# poti_encoder.net
KiCad netlist of a schematic drawn in EAGLE
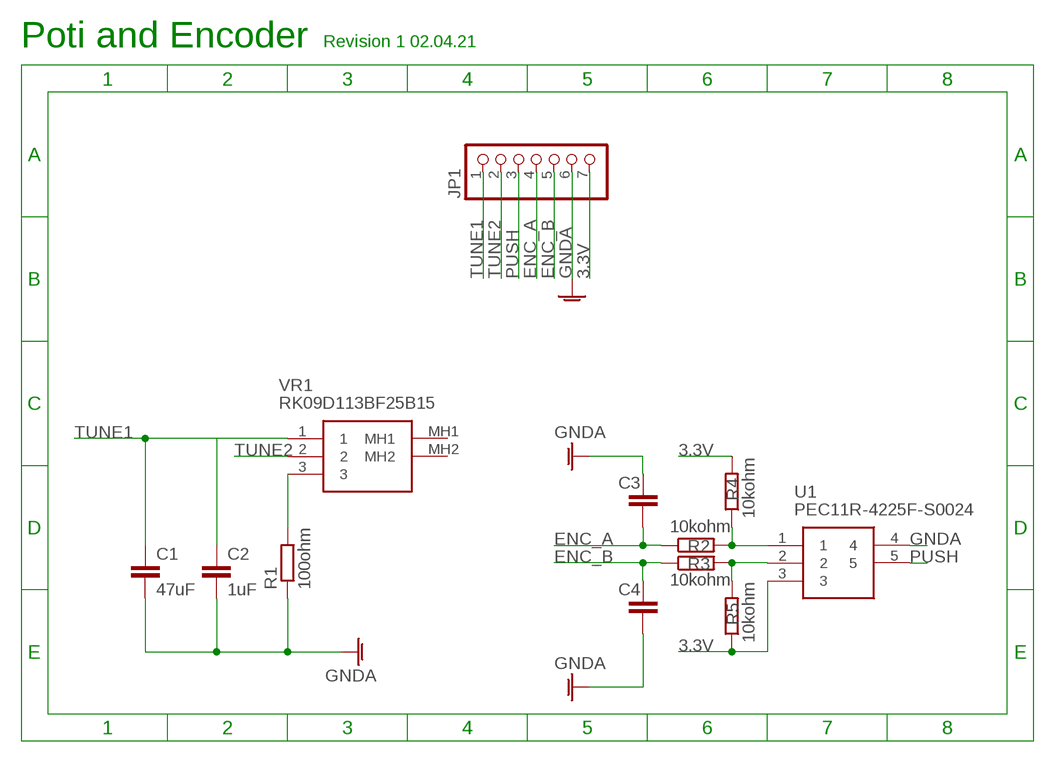
[diagram p0: schematic, sheet 1]

(export (version "E")
  (design (tool "Eeschema 10.0.6"))
  (components
    (comp (ref "C1")
      (value "47uF")
      (footprint "eagle-import:C1206")
      (libsource (lib "eagle-import") (part "C-EU_1206C1206"))
    )
    (comp (ref "C2")
      (value "1uF")
      (footprint "eagle-import:C0805")
      (libsource (lib "eagle-import") (part "C-EU_805C0805"))
    )
    (comp (ref "C3")
      (value "C-EU_805C0805")
      (footprint "eagle-import:C0805")
      (libsource (lib "eagle-import") (part "C-EU_805C0805"))
    )
    (comp (ref "C4")
      (value "C-EU_805C0805")
      (footprint "eagle-import:C0805")
      (libsource (lib "eagle-import") (part "C-EU_805C0805"))
    )
    (comp (ref "JP1")
      (value "PINHD-1X7")
      (footprint "eagle-import:1X07")
      (libsource (lib "eagle-import") (part "PINHD-1X7"))
    )
    (comp (ref "R1")
      (value "100ohm")
      (footprint "eagle-import:R0805")
      (libsource (lib "eagle-import") (part "R-EU_805R0805"))
    )
    (comp (ref "R2")
      (value "10kohm")
      (footprint "eagle-import:R0805")
      (libsource (lib "eagle-import") (part "R-EU_805R0805"))
    )
    (comp (ref "R3")
      (value "10kohm")
      (footprint "eagle-import:R0805")
      (libsource (lib "eagle-import") (part "R-EU_805R0805"))
    )
    (comp (ref "R4")
      (value "10kohm")
      (footprint "eagle-import:R0805")
      (libsource (lib "eagle-import") (part "R-EU_805R0805"))
    )
    (comp (ref "R5")
      (value "10kohm")
      (footprint "eagle-import:R0805")
      (libsource (lib "eagle-import") (part "R-EU_805R0805"))
    )
    (comp (ref "U1")
      (value "PEC11R-4225F-S0024")
      (footprint "eagle-import:PEC12R-4XXXF-SXXXX_1")
      (fields (field (name "MOUSER_PART_NUMBER") "652-PEC11R-4225F-S24"))
      (libsource (lib "eagle-import") (part "PEC11R-4225F-S0024"))
    )
    (comp (ref "VR1")
      (value "RK09D113BF25B15")
      (footprint "eagle-import:RK09D113BF25B15")
      (fields (field (name "MOUSER_PART_NUMBER") "688-RK09D113BF25B15"))
      (libsource (lib "eagle-import") (part "RK09D113BF25B15"))
    )
  )
  (nets
    (net (code "1") (name "/3.3V") (class "Default")
      (node (ref "JP1") (pin "7") (pinfunction "7_7") (pintype "passive"))
      (node (ref "R4") (pin "2") (pinfunction "2_2") (pintype "passive"))
      (node (ref "R5") (pin "1") (pinfunction "1_1") (pintype "passive"))
      (node (ref "U1") (pin "3") (pinfunction "3_3") (pintype "bidirectional"))
    )
    (net (code "2") (name "/ENC_A") (class "Default")
      (node (ref "C3") (pin "2") (pinfunction "2_2") (pintype "passive"))
      (node (ref "JP1") (pin "4") (pinfunction "4_4") (pintype "passive"))
      (node (ref "R2") (pin "1") (pinfunction "1_1") (pintype "passive"))
    )
    (net (code "3") (name "/ENC_B") (class "Default")
      (node (ref "C4") (pin "1") (pinfunction "1_1") (pintype "passive"))
      (node (ref "JP1") (pin "5") (pinfunction "5_5") (pintype "passive"))
      (node (ref "R3") (pin "1") (pinfunction "1_1") (pintype "passive"))
    )
    (net (code "4") (name "/PUSH") (class "Default")
      (node (ref "JP1") (pin "3") (pinfunction "3_3") (pintype "passive"))
      (node (ref "U1") (pin "5") (pinfunction "5_5") (pintype "bidirectional"))
    )
    (net (code "5") (name "/TUNE1") (class "Default")
      (node (ref "C1") (pin "1") (pinfunction "1_1") (pintype "passive"))
      (node (ref "C2") (pin "1") (pinfunction "1_1") (pintype "passive"))
      (node (ref "JP1") (pin "1") (pinfunction "1_1") (pintype "passive"))
      (node (ref "VR1") (pin "1") (pinfunction "1_1") (pintype "bidirectional"))
    )
    (net (code "6") (name "/TUNE2") (class "Default")
      (node (ref "JP1") (pin "2") (pinfunction "2_2") (pintype "passive"))
      (node (ref "VR1") (pin "2") (pinfunction "2_2") (pintype "bidirectional"))
    )
    (net (code "7") (name "GNDA") (class "Default")
      (node (ref "C1") (pin "2") (pinfunction "2_2") (pintype "passive"))
      (node (ref "C2") (pin "2") (pinfunction "2_2") (pintype "passive"))
      (node (ref "C3") (pin "1") (pinfunction "1_1") (pintype "passive"))
      (node (ref "C4") (pin "2") (pinfunction "2_2") (pintype "passive"))
      (node (ref "JP1") (pin "6") (pinfunction "6_6") (pintype "passive"))
      (node (ref "R1") (pin "1") (pinfunction "1_1") (pintype "passive"))
      (node (ref "U1") (pin "4") (pinfunction "4_4") (pintype "bidirectional"))
    )
    (net (code "8") (name "Net-(R1-Pad2)") (class "Default")
      (node (ref "R1") (pin "2") (pinfunction "2_2") (pintype "passive"))
      (node (ref "VR1") (pin "3") (pinfunction "3_3") (pintype "bidirectional"))
    )
    (net (code "9") (name "Net-(R2-Pad2)") (class "Default")
      (node (ref "R2") (pin "2") (pinfunction "2_2") (pintype "passive"))
      (node (ref "R4") (pin "1") (pinfunction "1_1") (pintype "passive"))
      (node (ref "U1") (pin "1") (pinfunction "1_1") (pintype "bidirectional"))
    )
    (net (code "10") (name "Net-(R3-Pad2)") (class "Default")
      (node (ref "R3") (pin "2") (pinfunction "2_2") (pintype "passive"))
      (node (ref "R5") (pin "2") (pinfunction "2_2") (pintype "passive"))
      (node (ref "U1") (pin "2") (pinfunction "2_2") (pintype "bidirectional"))
    )
    (net (code "11") (name "unconnected-(VR1-PadMH1)") (class "Default")
      (node (ref "VR1") (pin "MH1") (pinfunction "MH1_MH1") (pintype "bidirectional"))
    )
    (net (code "12") (name "unconnected-(VR1-PadMH2)") (class "Default")
      (node (ref "VR1") (pin "MH2") (pinfunction "MH2_MH2") (pintype "bidirectional"))
    )
  )
)
